# led2ch_v0_1.net
KiCad netlist of a schematic drawn in EAGLE
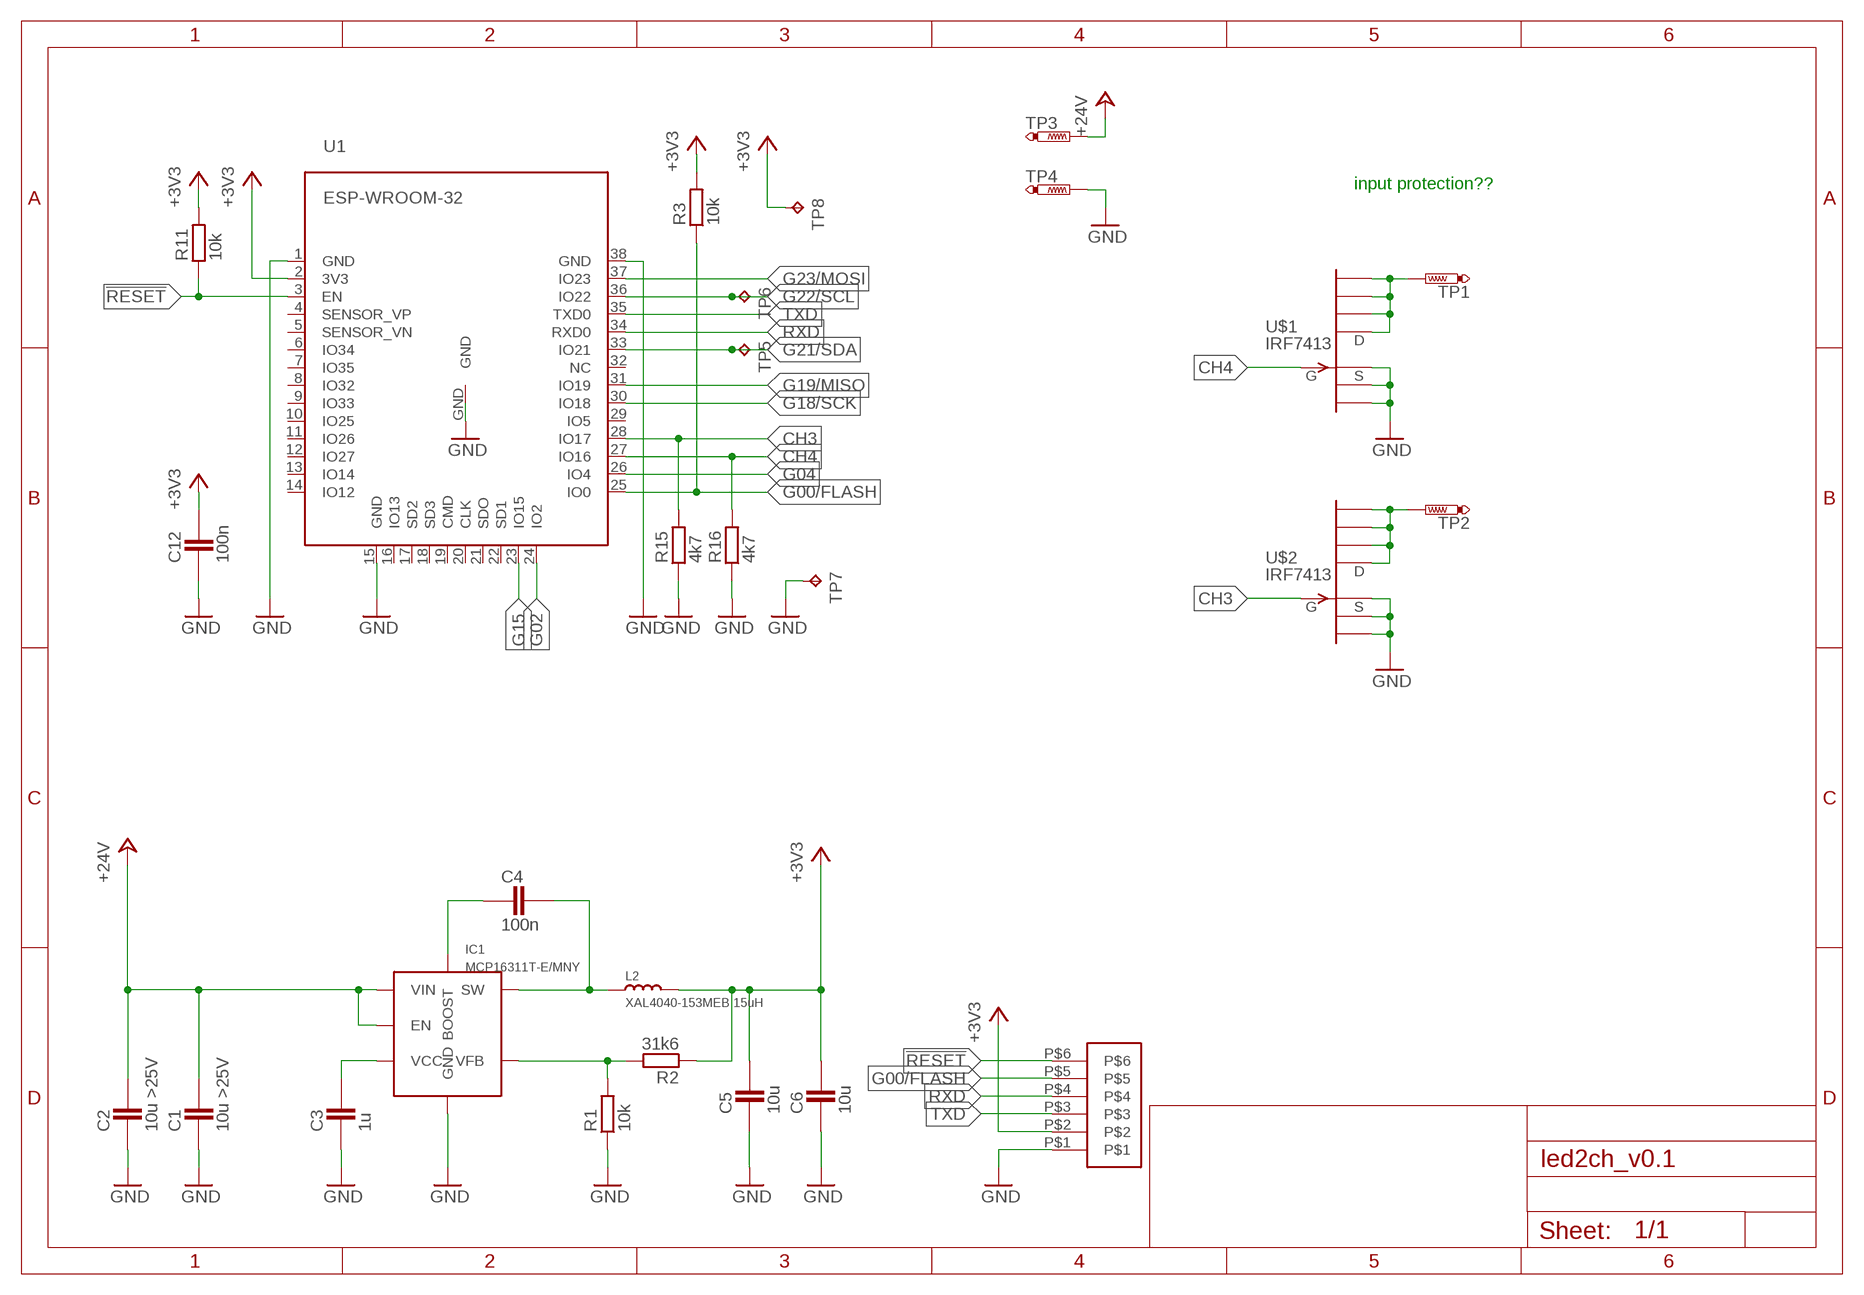
[diagram p0: schematic, sheet 1]

(export (version "E")
  (design (tool "Eeschema 10.0.6"))
  (components
    (comp (ref "C1")
      (value "10u >25V")
      (footprint "eagle-import:CAPC2012X145AN")
      (libsource (lib "eagle-import") (part "CAPACITOR_0805"))
    )
    (comp (ref "C2")
      (value "10u >25V")
      (footprint "eagle-import:CAPC2012X145AN")
      (libsource (lib "eagle-import") (part "CAPACITOR_0805"))
    )
    (comp (ref "C3")
      (value "1u")
      (footprint "eagle-import:CAPC1608X92N")
      (libsource (lib "eagle-import") (part "CAPACITOR_0603"))
    )
    (comp (ref "C4")
      (value "100n")
      (footprint "eagle-import:CAPC1005X60N")
      (libsource (lib "eagle-import") (part "CAPACITOR_0402"))
    )
    (comp (ref "C5")
      (value "10u")
      (footprint "eagle-import:CAPC2012X145AN")
      (libsource (lib "eagle-import") (part "CAPACITOR_0805"))
    )
    (comp (ref "C6")
      (value "10u")
      (footprint "eagle-import:CAPC2012X145AN")
      (libsource (lib "eagle-import") (part "CAPACITOR_0805"))
    )
    (comp (ref "C12")
      (value "100n")
      (footprint "eagle-import:CAPC1005X60N")
      (libsource (lib "eagle-import") (part "CAPACITOR_0402"))
    )
    (comp (ref "IC1")
      (value "MCP16311T-E/MNY")
      (footprint "eagle-import:TDFN8")
      (libsource (lib "eagle-import") (part "MCP16311-TDFN"))
    )
    (comp (ref "L2")
      (value "XAL4040-153MEB 15uH")
      (footprint "eagle-import:L0420")
      (fields (field (name "MPN") "SPD3D16-4R7M"))
      (libsource (lib "eagle-import") (part "SMD-POWER-INDUCTOR-4.7UH-20%-750MA(2P-3.9X3.9MM)"))
    )
    (comp (ref "R1")
      (value "10k")
      (footprint "eagle-import:RESC1005X40AN")
      (libsource (lib "eagle-import") (part "RESISTOR_0402"))
    )
    (comp (ref "R2")
      (value "31k6")
      (footprint "eagle-import:RESC1005X40AN")
      (libsource (lib "eagle-import") (part "RESISTOR_0402"))
    )
    (comp (ref "R3")
      (value "10k")
      (footprint "eagle-import:RESC1005X40AN")
      (libsource (lib "eagle-import") (part "RESISTOR_0402"))
    )
    (comp (ref "R11")
      (value "10k")
      (footprint "eagle-import:RESC1005X40AN")
      (libsource (lib "eagle-import") (part "RESISTOR_0402"))
    )
    (comp (ref "R15")
      (value "4k7")
      (footprint "eagle-import:RESC1005X40AN")
      (libsource (lib "eagle-import") (part "RESISTOR_0402"))
    )
    (comp (ref "R16")
      (value "4k7")
      (footprint "eagle-import:RESC1005X40AN")
      (libsource (lib "eagle-import") (part "RESISTOR_0402"))
    )
    (comp (ref "TP1")
      (value "PTR1B1,27")
      (footprint "eagle-import:B1,27")
      (libsource (lib "eagle-import") (part "PTR1B1,27"))
    )
    (comp (ref "TP2")
      (value "PTR1B1,27")
      (footprint "eagle-import:B1,27")
      (libsource (lib "eagle-import") (part "PTR1B1,27"))
    )
    (comp (ref "TP3")
      (value "PTR1B2,54")
      (footprint "eagle-import:B2,54")
      (libsource (lib "eagle-import") (part "PTR1B2,54"))
    )
    (comp (ref "TP4")
      (value "PTR1B2,54")
      (footprint "eagle-import:B2,54")
      (libsource (lib "eagle-import") (part "PTR1B2,54"))
    )
    (comp (ref "TP5")
      (value "TPB1,27")
      (footprint "eagle-import:B1,27")
      (libsource (lib "eagle-import") (part "TPB1,27"))
    )
    (comp (ref "TP6")
      (value "TPB1,27")
      (footprint "eagle-import:B1,27")
      (libsource (lib "eagle-import") (part "TPB1,27"))
    )
    (comp (ref "TP7")
      (value "TPB1,27")
      (footprint "eagle-import:B1,27")
      (libsource (lib "eagle-import") (part "TPB1,27"))
    )
    (comp (ref "TP8")
      (value "TPB1,27")
      (footprint "eagle-import:B1,27")
      (libsource (lib "eagle-import") (part "TPB1,27"))
    )
    (comp (ref "U$1")
      (value "IRF7413")
      (footprint "eagle-import:SO-8")
      (libsource (lib "eagle-import") (part "IRF7413"))
    )
    (comp (ref "U$2")
      (value "IRF7413")
      (footprint "eagle-import:SO-8")
      (libsource (lib "eagle-import") (part "IRF7413"))
    )
    (comp (ref "U$3")
      (value "3X2-2.00RM")
      (footprint "eagle-import:3X2-2.00RM")
      (libsource (lib "eagle-import") (part "3X2-2.00RM"))
    )
    (comp (ref "U1")
      (value "ESP-WROOM-32")
      (footprint "eagle-import:ESP-WROOM-32")
      (libsource (lib "eagle-import") (part "ESP-WROOM-32"))
    )
  )
  (nets
    (net (code "1") (name "+3V3") (class "Default")
      (node (ref "C12") (pin "2") (pinfunction "2_2") (pintype "passive"))
      (node (ref "C5") (pin "2") (pinfunction "2_2") (pintype "passive"))
      (node (ref "C6") (pin "2") (pinfunction "2_2") (pintype "passive"))
      (node (ref "L2") (pin "2") (pinfunction "2_2") (pintype "passive"))
      (node (ref "R11") (pin "2") (pinfunction "2_2") (pintype "passive"))
      (node (ref "R2") (pin "1") (pinfunction "1_1") (pintype "passive"))
      (node (ref "R3") (pin "2") (pinfunction "2_2") (pintype "passive"))
      (node (ref "TP8") (pin "TP") (pinfunction "TP_TP") (pintype "input"))
      (node (ref "U$3") (pin "P$2") (pinfunction "P$2_P$2") (pintype "bidirectional"))
      (node (ref "U1") (pin "2") (pinfunction "3V3_2") (pintype "bidirectional"))
    )
    (net (code "2") (name "+24V") (class "Default")
      (node (ref "C1") (pin "2") (pinfunction "2_2") (pintype "passive"))
      (node (ref "C2") (pin "2") (pinfunction "2_2") (pintype "passive"))
      (node (ref "IC1") (pin "P$3") (pinfunction "EN_P$3") (pintype "bidirectional"))
      (node (ref "IC1") (pin "P$4") (pinfunction "VIN_P$4") (pintype "bidirectional"))
      (node (ref "TP3") (pin "TP") (pinfunction "TP_TP") (pintype "input"))
    )
    (net (code "3") (name "/~{RESET}") (class "Default")
      (node (ref "R11") (pin "1") (pinfunction "1_1") (pintype "passive"))
      (node (ref "U$3") (pin "P$6") (pinfunction "P$6_P$6") (pintype "bidirectional"))
      (node (ref "U1") (pin "3") (pinfunction "EN_3") (pintype "bidirectional"))
    )
    (net (code "4") (name "CH3") (class "Default")
      (node (ref "R15") (pin "2") (pinfunction "2_2") (pintype "passive"))
      (node (ref "U$2") (pin "4") (pinfunction "G_4") (pintype "passive"))
      (node (ref "U1") (pin "28") (pinfunction "IO17_28") (pintype "bidirectional"))
    )
    (net (code "5") (name "CH4") (class "Default")
      (node (ref "R16") (pin "2") (pinfunction "2_2") (pintype "passive"))
      (node (ref "U$1") (pin "4") (pinfunction "G_4") (pintype "passive"))
      (node (ref "U1") (pin "27") (pinfunction "IO16_27") (pintype "bidirectional"))
    )
    (net (code "6") (name "G00{slash}FLASH") (class "Default")
      (node (ref "R3") (pin "1") (pinfunction "1_1") (pintype "passive"))
      (node (ref "U$3") (pin "P$5") (pinfunction "P$5_P$5") (pintype "bidirectional"))
      (node (ref "U1") (pin "25") (pinfunction "IO0_25") (pintype "bidirectional"))
    )
    (net (code "7") (name "G02") (class "Default")
      (node (ref "U1") (pin "24") (pinfunction "IO2_24") (pintype "bidirectional"))
    )
    (net (code "8") (name "G04") (class "Default")
      (node (ref "U1") (pin "26") (pinfunction "IO4_26") (pintype "bidirectional"))
    )
    (net (code "9") (name "G15") (class "Default")
      (node (ref "U1") (pin "23") (pinfunction "IO15_23") (pintype "bidirectional"))
    )
    (net (code "10") (name "G18{slash}SCK") (class "Default")
      (node (ref "U1") (pin "30") (pinfunction "IO18_30") (pintype "bidirectional"))
    )
    (net (code "11") (name "G19{slash}MISO") (class "Default")
      (node (ref "U1") (pin "31") (pinfunction "IO19_31") (pintype "bidirectional"))
    )
    (net (code "12") (name "G21{slash}SDA") (class "Default")
      (node (ref "TP5") (pin "TP") (pinfunction "TP_TP") (pintype "input"))
      (node (ref "U1") (pin "33") (pinfunction "IO21_33") (pintype "bidirectional"))
    )
    (net (code "13") (name "G22{slash}SCL") (class "Default")
      (node (ref "TP6") (pin "TP") (pinfunction "TP_TP") (pintype "input"))
      (node (ref "U1") (pin "36") (pinfunction "IO22_36") (pintype "bidirectional"))
    )
    (net (code "14") (name "G23{slash}MOSI") (class "Default")
      (node (ref "U1") (pin "37") (pinfunction "IO23_37") (pintype "bidirectional"))
    )
    (net (code "15") (name "GND") (class "Default")
      (node (ref "C1") (pin "1") (pinfunction "1_1") (pintype "passive"))
      (node (ref "C12") (pin "1") (pinfunction "1_1") (pintype "passive"))
      (node (ref "C2") (pin "1") (pinfunction "1_1") (pintype "passive"))
      (node (ref "C3") (pin "1") (pinfunction "1_1") (pintype "passive"))
      (node (ref "C5") (pin "1") (pinfunction "1_1") (pintype "passive"))
      (node (ref "C6") (pin "1") (pinfunction "1_1") (pintype "passive"))
      (node (ref "IC1") (pin "P$5") (pinfunction "GND_P$5") (pintype "bidirectional"))
      (node (ref "IC1") (pin "P$8") (pinfunction "GND_P$8") (pintype "bidirectional"))
      (node (ref "IC1") (pin "P$9") (pinfunction "GND_P$9") (pintype "bidirectional"))
      (node (ref "R1") (pin "1") (pinfunction "1_1") (pintype "passive"))
      (node (ref "R15") (pin "1") (pinfunction "1_1") (pintype "passive"))
      (node (ref "R16") (pin "1") (pinfunction "1_1") (pintype "passive"))
      (node (ref "TP4") (pin "TP") (pinfunction "TP_TP") (pintype "input"))
      (node (ref "TP7") (pin "TP") (pinfunction "TP_TP") (pintype "input"))
      (node (ref "U$1") (pin "1") (pinfunction "S_1") (pintype "passive"))
      (node (ref "U$1") (pin "2") (pinfunction "S1_2") (pintype "passive"))
      (node (ref "U$1") (pin "3") (pinfunction "S2_3") (pintype "passive"))
      (node (ref "U$2") (pin "1") (pinfunction "S_1") (pintype "passive"))
      (node (ref "U$2") (pin "2") (pinfunction "S1_2") (pintype "passive"))
      (node (ref "U$2") (pin "3") (pinfunction "S2_3") (pintype "passive"))
      (node (ref "U$3") (pin "P$1") (pinfunction "P$1_P$1") (pintype "bidirectional"))
      (node (ref "U1") (pin "1") (pinfunction "GND_1") (pintype "bidirectional"))
      (node (ref "U1") (pin "15") (pinfunction "GND_15") (pintype "bidirectional"))
      (node (ref "U1") (pin "38") (pinfunction "GND_38") (pintype "bidirectional"))
      (node (ref "U1") (pin "GND") (pinfunction "GND_GND") (pintype "bidirectional"))
    )
    (net (code "16") (name "Net-(IC1-BOOST)") (class "Default")
      (node (ref "C4") (pin "1") (pinfunction "1_1") (pintype "passive"))
      (node (ref "IC1") (pin "P$7") (pinfunction "BOOST_P$7") (pintype "bidirectional"))
    )
    (net (code "17") (name "Net-(IC1-SW)") (class "Default")
      (node (ref "C4") (pin "2") (pinfunction "2_2") (pintype "passive"))
      (node (ref "IC1") (pin "P$6") (pinfunction "SW_P$6") (pintype "bidirectional"))
      (node (ref "L2") (pin "1") (pinfunction "1_1") (pintype "passive"))
    )
    (net (code "18") (name "Net-(IC1-VCC)") (class "Default")
      (node (ref "C3") (pin "2") (pinfunction "2_2") (pintype "passive"))
      (node (ref "IC1") (pin "P$2") (pinfunction "VCC_P$2") (pintype "bidirectional"))
    )
    (net (code "19") (name "Net-(IC1-VFB)") (class "Default")
      (node (ref "IC1") (pin "P$1") (pinfunction "VFB_P$1") (pintype "bidirectional"))
      (node (ref "R1") (pin "2") (pinfunction "2_2") (pintype "passive"))
      (node (ref "R2") (pin "2") (pinfunction "2_2") (pintype "passive"))
    )
    (net (code "20") (name "Net-(U$1-D)") (class "Default")
      (node (ref "TP1") (pin "TP") (pinfunction "TP_TP") (pintype "input"))
      (node (ref "U$1") (pin "5") (pinfunction "D_5") (pintype "passive"))
      (node (ref "U$1") (pin "6") (pinfunction "D1_6") (pintype "passive"))
      (node (ref "U$1") (pin "7") (pinfunction "D2_7") (pintype "passive"))
      (node (ref "U$1") (pin "8") (pinfunction "D3_8") (pintype "passive"))
    )
    (net (code "21") (name "Net-(U$2-D)") (class "Default")
      (node (ref "TP2") (pin "TP") (pinfunction "TP_TP") (pintype "input"))
      (node (ref "U$2") (pin "5") (pinfunction "D_5") (pintype "passive"))
      (node (ref "U$2") (pin "6") (pinfunction "D1_6") (pintype "passive"))
      (node (ref "U$2") (pin "7") (pinfunction "D2_7") (pintype "passive"))
      (node (ref "U$2") (pin "8") (pinfunction "D3_8") (pintype "passive"))
    )
    (net (code "22") (name "RXD") (class "Default")
      (node (ref "U$3") (pin "P$4") (pinfunction "P$4_P$4") (pintype "bidirectional"))
      (node (ref "U1") (pin "34") (pinfunction "RXD0_34") (pintype "bidirectional"))
    )
    (net (code "23") (name "TXD") (class "Default")
      (node (ref "U$3") (pin "P$3") (pinfunction "P$3_P$3") (pintype "bidirectional"))
      (node (ref "U1") (pin "35") (pinfunction "TXD0_35") (pintype "bidirectional"))
    )
    (net (code "24") (name "unconnected-(U1-CLK-Pad20)") (class "Default")
      (node (ref "U1") (pin "20") (pinfunction "CLK_20") (pintype "bidirectional"))
    )
    (net (code "25") (name "unconnected-(U1-CMD-Pad19)") (class "Default")
      (node (ref "U1") (pin "19") (pinfunction "CMD_19") (pintype "bidirectional"))
    )
    (net (code "26") (name "unconnected-(U1-IO5-Pad29)") (class "Default")
      (node (ref "U1") (pin "29") (pinfunction "IO5_29") (pintype "bidirectional"))
    )
    (net (code "27") (name "unconnected-(U1-IO12-Pad14)") (class "Default")
      (node (ref "U1") (pin "14") (pinfunction "IO12_14") (pintype "bidirectional"))
    )
    (net (code "28") (name "unconnected-(U1-IO13-Pad16)") (class "Default")
      (node (ref "U1") (pin "16") (pinfunction "IO13_16") (pintype "bidirectional"))
    )
    (net (code "29") (name "unconnected-(U1-IO14-Pad13)") (class "Default")
      (node (ref "U1") (pin "13") (pinfunction "IO14_13") (pintype "bidirectional"))
    )
    (net (code "30") (name "unconnected-(U1-IO25-Pad10)") (class "Default")
      (node (ref "U1") (pin "10") (pinfunction "IO25_10") (pintype "bidirectional"))
    )
    (net (code "31") (name "unconnected-(U1-IO26-Pad11)") (class "Default")
      (node (ref "U1") (pin "11") (pinfunction "IO26_11") (pintype "bidirectional"))
    )
    (net (code "32") (name "unconnected-(U1-IO27-Pad12)") (class "Default")
      (node (ref "U1") (pin "12") (pinfunction "IO27_12") (pintype "bidirectional"))
    )
    (net (code "33") (name "unconnected-(U1-IO32-Pad8)") (class "Default")
      (node (ref "U1") (pin "8") (pinfunction "IO32_8") (pintype "bidirectional"))
    )
    (net (code "34") (name "unconnected-(U1-IO33-Pad9)") (class "Default")
      (node (ref "U1") (pin "9") (pinfunction "IO33_9") (pintype "bidirectional"))
    )
    (net (code "35") (name "unconnected-(U1-IO34-Pad6)") (class "Default")
      (node (ref "U1") (pin "6") (pinfunction "IO34_6") (pintype "bidirectional"))
    )
    (net (code "36") (name "unconnected-(U1-IO35-Pad7)") (class "Default")
      (node (ref "U1") (pin "7") (pinfunction "IO35_7") (pintype "bidirectional"))
    )
    (net (code "37") (name "unconnected-(U1-NC-Pad32)") (class "Default")
      (node (ref "U1") (pin "32") (pinfunction "NC_32") (pintype "bidirectional"))
    )
    (net (code "38") (name "unconnected-(U1-SD1-Pad22)") (class "Default")
      (node (ref "U1") (pin "22") (pinfunction "SD1_22") (pintype "bidirectional"))
    )
    (net (code "39") (name "unconnected-(U1-SD2-Pad17)") (class "Default")
      (node (ref "U1") (pin "17") (pinfunction "SD2_17") (pintype "bidirectional"))
    )
    (net (code "40") (name "unconnected-(U1-SD3-Pad18)") (class "Default")
      (node (ref "U1") (pin "18") (pinfunction "SD3_18") (pintype "bidirectional"))
    )
    (net (code "41") (name "unconnected-(U1-SDO-Pad21)") (class "Default")
      (node (ref "U1") (pin "21") (pinfunction "SDO_21") (pintype "bidirectional"))
    )
    (net (code "42") (name "unconnected-(U1-SENSOR_VN-Pad5)") (class "Default")
      (node (ref "U1") (pin "5") (pinfunction "SENSOR_VN_5") (pintype "bidirectional"))
    )
    (net (code "43") (name "unconnected-(U1-SENSOR_VP-Pad4)") (class "Default")
      (node (ref "U1") (pin "4") (pinfunction "SENSOR_VP_4") (pintype "bidirectional"))
    )
  )
)
